# interfaces.net
KiCad netlist of a schematic drawn in Altium Designer
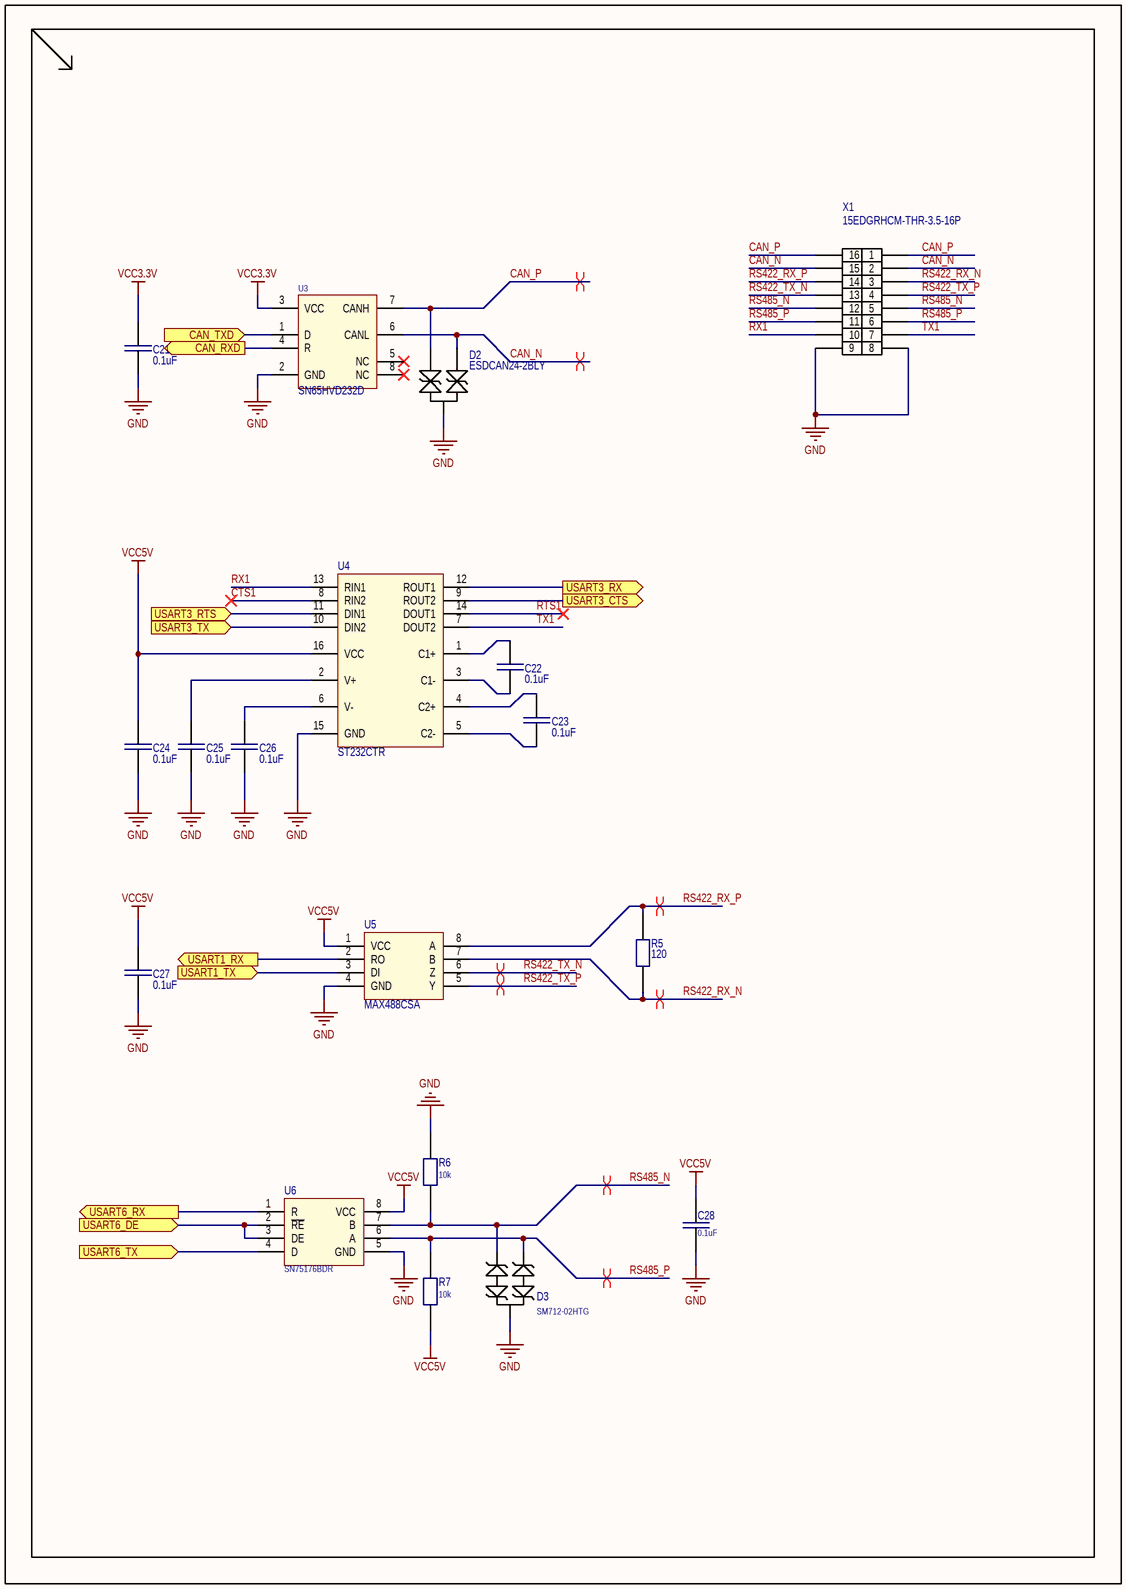
[diagram p0: interfaces.schdoc]

(export (version "E")
  (design (tool "Eeschema 10.0.6"))
  (components
    (comp (ref "C21")
      (value "0.1uF")
      (footprint "C_0603")
      (description "Capacitor")
      (fields (field (name "PART NUMBER") "CC0603KPX7R9BB104"))
      (libsource (lib "capacitors") (part "CAP_SMD"))
    )
    (comp (ref "C22")
      (value "0.1uF")
      (footprint "C_0603")
      (description "Capacitor")
      (fields (field (name "PART") "CC0603KPX7R9BB104"))
      (libsource (lib "capacitors") (part "C0603"))
    )
    (comp (ref "C23")
      (value "0.1uF")
      (footprint "C_0603")
      (description "Capacitor")
      (fields (field (name "PART") "CC0603KPX7R9BB104"))
      (libsource (lib "capacitors") (part "C0603"))
    )
    (comp (ref "C24")
      (value "0.1uF")
      (footprint "C_0603")
      (description "Capacitor")
      (fields (field (name "PART") "CC0603KPX7R9BB104"))
      (libsource (lib "capacitors") (part "C0603"))
    )
    (comp (ref "C25")
      (value "0.1uF")
      (footprint "C_0603")
      (description "Capacitor")
      (fields (field (name "PART") "CC0603KPX7R9BB104"))
      (libsource (lib "capacitors") (part "C0603"))
    )
    (comp (ref "C26")
      (value "0.1uF")
      (footprint "C_0603")
      (description "Capacitor")
      (fields (field (name "PART") "CC0603KPX7R9BB104"))
      (libsource (lib "capacitors") (part "C0603"))
    )
    (comp (ref "C27")
      (value "0.1uF")
      (footprint "C_0603")
      (description "Capacitor")
      (fields (field (name "PART NUMBER") "CC0603KPX7R9BB104"))
      (libsource (lib "capacitors") (part "CAP_SMD"))
    )
    (comp (ref "C28")
      (value "0.1uF")
      (footprint "C_0603")
      (description "Capacitor")
      (fields (field (name "PART NUMBER") "CC0603KPX7R9BB104"))
      (libsource (lib "capacitors") (part "CAP_SMD"))
    )
    (comp (ref "D2")
      (value "ESDCAN24-2BLY")
      (footprint "diode:SOT23")
      (description "ESD")
      (libsource (lib "diode") (part "ESD_CAN"))
    )
    (comp (ref "D3")
      (value "SM712-02HTG")
      (footprint "diode:SOT23")
      (description "ESD")
      (libsource (lib "diode") (part "ESD"))
    )
    (comp (ref "R5")
      (value "120")
      (footprint "R_0603")
      (description "Resistor")
      (fields (field (name "PART NUMBER") "RC0603FR-07120RL"))
      (libsource (lib "resistors") (part "RES_SMD"))
    )
    (comp (ref "R6")
      (value "10k")
      (footprint "R_0603")
      (description "Resistor")
      (fields (field (name "PART NUMBER") "RC0603FR-0710KL"))
      (libsource (lib "resistors") (part "RES_SMD"))
    )
    (comp (ref "R7")
      (value "10k")
      (footprint "R_0603")
      (description "Resistor")
      (fields (field (name "PART NUMBER") "RC0603FR-0710KL"))
      (libsource (lib "resistors") (part "RES_SMD"))
    )
    (comp (ref "U3")
      (value "SN65HVD232D")
      (footprint "SO-8_M")
      (description "CAN_transiever")
      (libsource (lib "discret_ic") (part "SN65HVD232D"))
    )
    (comp (ref "U4")
      (value "ST232CTR")
      (footprint "TSSOP16_STM")
      (description "No Description Available")
      (fields (field (name "COPYRIGHT") "Copyright (C) 2022 Ultra Librarian. All rights reserved."))
      (libsource (lib "discret_ic") (part "ST232CTR"))
    )
    (comp (ref "U5")
      (value "MAX488CSA")
      (footprint "discret_ic:SO-8_M")
      (description "RS485 Full Duplex Convertor")
      (fields (field (name "ALTERNATIVE PART") "ADM4855ARZ"))
      (libsource (lib "discret_ic") (part "ADM4855ARZ"))
    )
    (comp (ref "U6")
      (value "SN75176BDR")
      (footprint "SO-8")
      (description "RS485 Half Duplex Convertor")
      (libsource (lib "discret_ic") (part "SN75176BDR"))
    )
    (comp (ref "X1")
      (value "15EDGRHCM-THR-3.5-16P")
      (footprint "DMC 1,5/ 8-G1F-3,5-LR P20THR / 1787072")
      (libsource (lib "connectors_socets") (part "DMC 1,5/ 8-G1F-3,5-LR P20THR / 1787072"))
    )
  )
  (nets
    (net (code "1") (name "/CAN_N") (class "Default")
      (node (ref "D2") (pin "2") (pinfunction "2_2") (pintype "passive"))
      (node (ref "U3") (pin "6") (pinfunction "CANL_6") (pintype "passive"))
      (node (ref "X1") (pin "15") (pinfunction "15_15") (pintype "passive"))
      (node (ref "X1") (pin "2") (pinfunction "2_2") (pintype "passive"))
    )
    (net (code "2") (name "/CAN_P") (class "Default")
      (node (ref "D2") (pin "1") (pinfunction "1_1") (pintype "passive"))
      (node (ref "U3") (pin "7") (pinfunction "CANH_7") (pintype "passive"))
      (node (ref "X1") (pin "1") (pinfunction "1_1") (pintype "passive"))
      (node (ref "X1") (pin "16") (pinfunction "16_16") (pintype "passive"))
    )
    (net (code "3") (name "/CAN_RXD") (class "Default")
      (node (ref "U3") (pin "4") (pinfunction "R_4") (pintype "passive"))
    )
    (net (code "4") (name "/CAN_TXD") (class "Default")
      (node (ref "U3") (pin "1") (pinfunction "D_1") (pintype "passive"))
    )
    (net (code "5") (name "/CTS1") (class "Default")
      (node (ref "U4") (pin "8") (pinfunction "RIN2_8") (pintype "passive+no_connect"))
    )
    (net (code "6") (name "/RS422_RX_N") (class "Default")
      (node (ref "R5") (pin "2") (pinfunction "2_2") (pintype "passive"))
      (node (ref "U5") (pin "7") (pinfunction "B_7") (pintype "passive"))
      (node (ref "X1") (pin "3") (pinfunction "3_3") (pintype "passive"))
    )
    (net (code "7") (name "/RS422_RX_P") (class "Default")
      (node (ref "R5") (pin "1") (pinfunction "1_1") (pintype "passive"))
      (node (ref "U5") (pin "8") (pinfunction "A_8") (pintype "passive"))
      (node (ref "X1") (pin "14") (pinfunction "14_14") (pintype "passive"))
    )
    (net (code "8") (name "/RS422_TX_N") (class "Default")
      (node (ref "U5") (pin "6") (pinfunction "Z_6") (pintype "passive"))
      (node (ref "X1") (pin "13") (pinfunction "13_13") (pintype "passive"))
    )
    (net (code "9") (name "/RS422_TX_P") (class "Default")
      (node (ref "U5") (pin "5") (pinfunction "Y_5") (pintype "passive"))
      (node (ref "X1") (pin "4") (pinfunction "4_4") (pintype "passive"))
    )
    (net (code "10") (name "/RS485_N") (class "Default")
      (node (ref "D3") (pin "1") (pinfunction "1_1") (pintype "passive"))
      (node (ref "R6") (pin "1") (pinfunction "1_1") (pintype "passive"))
      (node (ref "U6") (pin "7") (pinfunction "B_7") (pintype "passive"))
      (node (ref "X1") (pin "12") (pinfunction "12_12") (pintype "passive"))
      (node (ref "X1") (pin "5") (pinfunction "5_5") (pintype "passive"))
    )
    (net (code "11") (name "/RS485_P") (class "Default")
      (node (ref "D3") (pin "2") (pinfunction "2_2") (pintype "passive"))
      (node (ref "R7") (pin "2") (pinfunction "2_2") (pintype "passive"))
      (node (ref "U6") (pin "6") (pinfunction "A_6") (pintype "passive"))
      (node (ref "X1") (pin "11") (pinfunction "11_11") (pintype "passive"))
      (node (ref "X1") (pin "6") (pinfunction "6_6") (pintype "passive"))
    )
    (net (code "12") (name "/RTS1") (class "Default")
      (node (ref "U4") (pin "14") (pinfunction "DOUT1_14") (pintype "passive+no_connect"))
    )
    (net (code "13") (name "/RX1") (class "Default")
      (node (ref "U4") (pin "13") (pinfunction "RIN1_13") (pintype "passive"))
      (node (ref "X1") (pin "10") (pinfunction "10_10") (pintype "passive"))
    )
    (net (code "14") (name "/TX1") (class "Default")
      (node (ref "U4") (pin "7") (pinfunction "DOUT2_7") (pintype "passive"))
      (node (ref "X1") (pin "7") (pinfunction "7_7") (pintype "passive"))
    )
    (net (code "15") (name "/USART1_RX") (class "Default")
      (node (ref "U5") (pin "2") (pinfunction "RO_2") (pintype "passive"))
    )
    (net (code "16") (name "/USART1_TX") (class "Default")
      (node (ref "U5") (pin "3") (pinfunction "DI_3") (pintype "passive"))
    )
    (net (code "17") (name "/USART3_CTS") (class "Default")
      (node (ref "U4") (pin "9") (pinfunction "ROUT2_9") (pintype "passive"))
    )
    (net (code "18") (name "/USART3_RTS") (class "Default")
      (node (ref "U4") (pin "11") (pinfunction "DIN1_11") (pintype "passive"))
    )
    (net (code "19") (name "/USART3_RX") (class "Default")
      (node (ref "U4") (pin "12") (pinfunction "ROUT1_12") (pintype "passive"))
    )
    (net (code "20") (name "/USART3_TX") (class "Default")
      (node (ref "U4") (pin "10") (pinfunction "DIN2_10") (pintype "passive"))
    )
    (net (code "21") (name "/USART6_DE") (class "Default")
      (node (ref "U6") (pin "2") (pinfunction "~{RE}_2") (pintype "passive"))
      (node (ref "U6") (pin "3") (pinfunction "DE_3") (pintype "passive"))
    )
    (net (code "22") (name "/USART6_RX") (class "Default")
      (node (ref "U6") (pin "1") (pinfunction "R_1") (pintype "passive"))
    )
    (net (code "23") (name "/USART6_TX") (class "Default")
      (node (ref "U6") (pin "4") (pinfunction "D_4") (pintype "passive"))
    )
    (net (code "24") (name "GND") (class "Default")
      (node (ref "C21") (pin "1") (pinfunction "1_1") (pintype "passive"))
      (node (ref "C24") (pin "1") (pinfunction "1_1") (pintype "passive"))
      (node (ref "C25") (pin "1") (pinfunction "1_1") (pintype "passive"))
      (node (ref "C26") (pin "1") (pinfunction "1_1") (pintype "passive"))
      (node (ref "C27") (pin "1") (pinfunction "1_1") (pintype "passive"))
      (node (ref "C28") (pin "1") (pinfunction "1_1") (pintype "passive"))
      (node (ref "D2") (pin "3") (pinfunction "3_3") (pintype "passive"))
      (node (ref "D3") (pin "3") (pinfunction "3_3") (pintype "passive"))
      (node (ref "R6") (pin "2") (pinfunction "2_2") (pintype "passive"))
      (node (ref "U3") (pin "2") (pinfunction "GND_2") (pintype "passive"))
      (node (ref "U4") (pin "15") (pinfunction "GND_15") (pintype "passive"))
      (node (ref "U5") (pin "4") (pinfunction "GND_4") (pintype "passive"))
      (node (ref "U6") (pin "5") (pinfunction "GND_5") (pintype "passive"))
      (node (ref "X1") (pin "8") (pinfunction "8_8") (pintype "passive"))
      (node (ref "X1") (pin "9") (pinfunction "9_9") (pintype "passive"))
    )
    (net (code "25") (name "Net-(U4-C1+)") (class "Default")
      (node (ref "C22") (pin "1") (pinfunction "1_1") (pintype "passive"))
      (node (ref "U4") (pin "1") (pinfunction "C1+_1") (pintype "passive"))
    )
    (net (code "26") (name "Net-(U4-C1-)") (class "Default")
      (node (ref "C22") (pin "2") (pinfunction "2_2") (pintype "passive"))
      (node (ref "U4") (pin "3") (pinfunction "C1-_3") (pintype "passive"))
    )
    (net (code "27") (name "Net-(U4-C2+)") (class "Default")
      (node (ref "C23") (pin "1") (pinfunction "1_1") (pintype "passive"))
      (node (ref "U4") (pin "4") (pinfunction "C2+_4") (pintype "passive"))
    )
    (net (code "28") (name "Net-(U4-C2-)") (class "Default")
      (node (ref "C23") (pin "2") (pinfunction "2_2") (pintype "passive"))
      (node (ref "U4") (pin "5") (pinfunction "C2-_5") (pintype "passive"))
    )
    (net (code "29") (name "Net-(U4-V+)") (class "Default")
      (node (ref "C25") (pin "2") (pinfunction "2_2") (pintype "passive"))
      (node (ref "U4") (pin "2") (pinfunction "V+_2") (pintype "passive"))
    )
    (net (code "30") (name "Net-(U4-V-)") (class "Default")
      (node (ref "C26") (pin "2") (pinfunction "2_2") (pintype "passive"))
      (node (ref "U4") (pin "6") (pinfunction "V-_6") (pintype "passive"))
    )
    (net (code "31") (name "VCC3.3V") (class "Default")
      (node (ref "C21") (pin "2") (pinfunction "2_2") (pintype "passive"))
      (node (ref "U3") (pin "3") (pinfunction "VCC_3") (pintype "passive"))
    )
    (net (code "32") (name "VCC5V") (class "Default")
      (node (ref "C24") (pin "2") (pinfunction "2_2") (pintype "passive"))
      (node (ref "C27") (pin "2") (pinfunction "2_2") (pintype "passive"))
      (node (ref "C28") (pin "2") (pinfunction "2_2") (pintype "passive"))
      (node (ref "R7") (pin "1") (pinfunction "1_1") (pintype "passive"))
      (node (ref "U4") (pin "16") (pinfunction "VCC_16") (pintype "passive"))
      (node (ref "U5") (pin "1") (pinfunction "VCC_1") (pintype "passive"))
      (node (ref "U6") (pin "8") (pinfunction "VCC_8") (pintype "passive"))
    )
    (net (code "33") (name "unconnected-(U3-NC-Pad5)") (class "Default")
      (node (ref "U3") (pin "5") (pinfunction "NC_5") (pintype "passive+no_connect"))
    )
    (net (code "34") (name "unconnected-(U3-NC-Pad8)") (class "Default")
      (node (ref "U3") (pin "8") (pinfunction "NC_8") (pintype "passive+no_connect"))
    )
  )
)
